# Wisp_v02.net
KiCad netlist of a schematic drawn in EAGLE
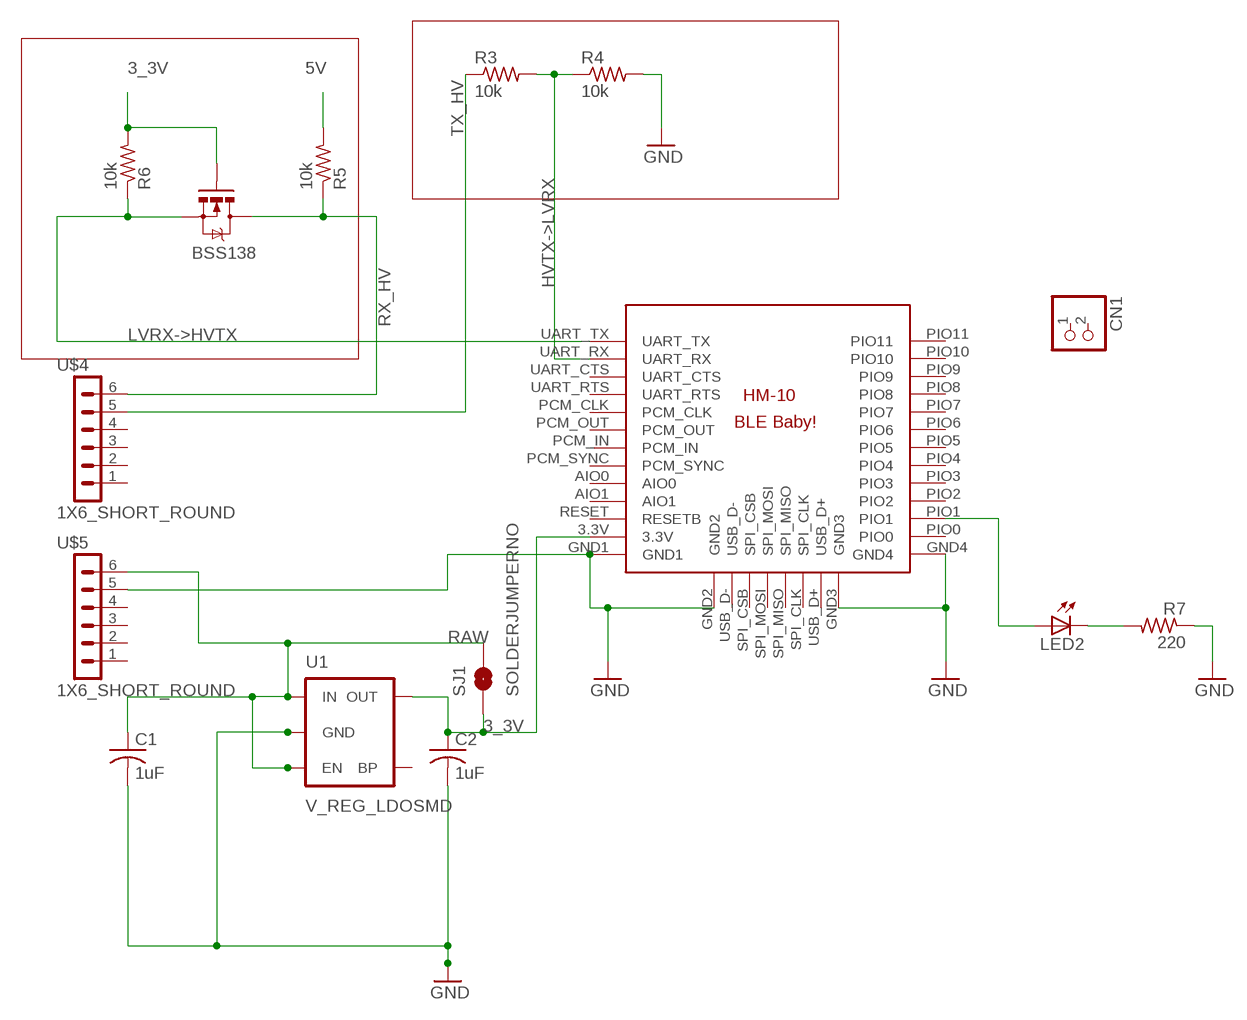
[diagram p0: schematic, sheet 1]

(export (version "E")
  (design (tool "Eeschema 10.0.6"))
  (components
    (comp (ref "BSS138")
      (value "MOSFET-NCHANNELSMD")
      (footprint "eagle-import:SOT23-3")
      (libsource (lib "eagle-import") (part "MOSFET-NCHANNELSMD"))
    )
    (comp (ref "C1")
      (value "1uF")
      (footprint "eagle-import:C0805K")
      (libsource (lib "eagle-import") (part "C-USC0805K"))
    )
    (comp (ref "C2")
      (value "1uF")
      (footprint "eagle-import:C0805K")
      (libsource (lib "eagle-import") (part "C-USC0805K"))
    )
    (comp (ref "CN1")
      (value "JST_2PIN-SMT")
      (footprint "eagle-import:JST-PH-2-SMT")
      (libsource (lib "eagle-import") (part "JST_2PIN-SMT"))
    )
    (comp (ref "LED2")
      (value "LED0603")
      (footprint "eagle-import:LED-0603")
      (libsource (lib "eagle-import") (part "LED0603"))
    )
    (comp (ref "R3")
      (value "10k")
      (footprint "eagle-import:M0805")
      (libsource (lib "eagle-import") (part "R-US_M0805"))
    )
    (comp (ref "R4")
      (value "10k")
      (footprint "eagle-import:M0805")
      (libsource (lib "eagle-import") (part "R-US_M0805"))
    )
    (comp (ref "R5")
      (value "10k")
      (footprint "eagle-import:M0805")
      (libsource (lib "eagle-import") (part "R-US_M0805"))
    )
    (comp (ref "R6")
      (value "10k")
      (footprint "eagle-import:M0805")
      (libsource (lib "eagle-import") (part "R-US_M0805"))
    )
    (comp (ref "R7")
      (value "220")
      (footprint "eagle-import:M0805")
      (libsource (lib "eagle-import") (part "R-US_M0805"))
    )
    (comp (ref "SJ1")
      (value "SOLDERJUMPERNO")
      (footprint "eagle-import:SJ_2S-NO")
      (libsource (lib "eagle-import") (part "SOLDERJUMPERNO"))
    )
    (comp (ref "U$1")
      (value "BLE-HM-10")
      (footprint "eagle-import:BLE-HM-10")
      (libsource (lib "eagle-import") (part "BLE-HM-10"))
    )
    (comp (ref "U$4")
      (value "1X6_SHORT_ROUND")
      (footprint "eagle-import:1X6_SHORT_ROUND")
      (libsource (lib "eagle-import") (part "1X6_SHORT_ROUND"))
    )
    (comp (ref "U$5")
      (value "1X6_SHORT_ROUND")
      (footprint "eagle-import:1X6_SHORT_ROUND")
      (libsource (lib "eagle-import") (part "1X6_SHORT_ROUND"))
    )
    (comp (ref "U1")
      (value "V_REG_LDOSMD")
      (footprint "eagle-import:SOT23-5")
      (libsource (lib "eagle-import") (part "V_REG_LDOSMD"))
    )
  )
  (nets
    (net (code "1") (name "/3_3V") (class "Default")
      (node (ref "BSS138") (pin "1") (pinfunction "G_1") (pintype "passive"))
      (node (ref "C2") (pin "1") (pinfunction "1_1") (pintype "passive"))
      (node (ref "R6") (pin "2") (pinfunction "2_2") (pintype "passive"))
      (node (ref "SJ1") (pin "1") (pinfunction "1_1") (pintype "passive"))
      (node (ref "U$1") (pin "3.3V") (pinfunction "3.3V_3.3V") (pintype "bidirectional"))
      (node (ref "U1") (pin "5") (pinfunction "OUT_5") (pintype "passive"))
    )
    (net (code "2") (name "/5V") (class "Default")
      (node (ref "R5") (pin "2") (pinfunction "2_2") (pintype "passive"))
    )
    (net (code "3") (name "/HVTX->LVRX") (class "Default")
      (node (ref "R3") (pin "2") (pinfunction "2_2") (pintype "passive"))
      (node (ref "R4") (pin "1") (pinfunction "1_1") (pintype "passive"))
      (node (ref "U$1") (pin "UART_RX") (pinfunction "UART_RX_UART_RX") (pintype "bidirectional"))
    )
    (net (code "4") (name "/LVRX->HVTX") (class "Default")
      (node (ref "BSS138") (pin "2") (pinfunction "S_2") (pintype "passive"))
      (node (ref "R6") (pin "1") (pinfunction "1_1") (pintype "passive"))
      (node (ref "U$1") (pin "UART_TX") (pinfunction "UART_TX_UART_TX") (pintype "bidirectional"))
    )
    (net (code "5") (name "/RAW") (class "Default")
      (node (ref "C1") (pin "1") (pinfunction "1_1") (pintype "passive"))
      (node (ref "SJ1") (pin "2") (pinfunction "2_2") (pintype "passive"))
      (node (ref "U$5") (pin "6") (pinfunction "6_6") (pintype "passive"))
      (node (ref "U1") (pin "1") (pinfunction "IN_1") (pintype "input"))
      (node (ref "U1") (pin "3") (pinfunction "EN_3") (pintype "input"))
    )
    (net (code "6") (name "/RX_HV") (class "Default")
      (node (ref "BSS138") (pin "3") (pinfunction "D_3") (pintype "passive"))
      (node (ref "R5") (pin "1") (pinfunction "1_1") (pintype "passive"))
      (node (ref "U$4") (pin "6") (pinfunction "6_6") (pintype "passive"))
    )
    (net (code "7") (name "/TX_HV") (class "Default")
      (node (ref "R3") (pin "1") (pinfunction "1_1") (pintype "passive"))
      (node (ref "U$4") (pin "5") (pinfunction "5_5") (pintype "passive"))
    )
    (net (code "8") (name "GND") (class "Default")
      (node (ref "C1") (pin "2") (pinfunction "2_2") (pintype "passive"))
      (node (ref "C2") (pin "2") (pinfunction "2_2") (pintype "passive"))
      (node (ref "R4") (pin "2") (pinfunction "2_2") (pintype "passive"))
      (node (ref "R7") (pin "1") (pinfunction "1_1") (pintype "passive"))
      (node (ref "U$1") (pin "GND1") (pinfunction "GND1_GND1") (pintype "bidirectional"))
      (node (ref "U$1") (pin "GND2") (pinfunction "GND2_GND2") (pintype "bidirectional"))
      (node (ref "U$1") (pin "GND3") (pinfunction "GND3_GND3") (pintype "bidirectional"))
      (node (ref "U$1") (pin "GND4") (pinfunction "GND4_GND4") (pintype "bidirectional"))
      (node (ref "U$5") (pin "5") (pinfunction "5_5") (pintype "passive"))
      (node (ref "U1") (pin "2") (pinfunction "GND_2") (pintype "input"))
    )
    (net (code "9") (name "Net-(LED2-PadA)") (class "Default")
      (node (ref "LED2") (pin "A") (pinfunction "A_A") (pintype "passive"))
      (node (ref "U$1") (pin "PIO1") (pinfunction "PIO1_PIO1") (pintype "bidirectional"))
    )
    (net (code "10") (name "Net-(LED2-PadC)") (class "Default")
      (node (ref "LED2") (pin "C") (pinfunction "C_C") (pintype "passive"))
      (node (ref "R7") (pin "2") (pinfunction "2_2") (pintype "passive"))
    )
    (net (code "11") (name "unconnected-(CN1-1-Pad2)") (class "Default")
      (node (ref "CN1") (pin "2") (pinfunction "1_2") (pintype "passive"))
    )
    (net (code "12") (name "unconnected-(CN1-2-Pad1)") (class "Default")
      (node (ref "CN1") (pin "1") (pinfunction "2_1") (pintype "passive"))
    )
    (net (code "13") (name "unconnected-(U$1-PadAIO0)") (class "Default")
      (node (ref "U$1") (pin "AIO0") (pinfunction "AIO0_AIO0") (pintype "bidirectional"))
    )
    (net (code "14") (name "unconnected-(U$1-PadAIO1)") (class "Default")
      (node (ref "U$1") (pin "AIO1") (pinfunction "AIO1_AIO1") (pintype "bidirectional"))
    )
    (net (code "15") (name "unconnected-(U$1-PadPCM_CLK)") (class "Default")
      (node (ref "U$1") (pin "PCM_CLK") (pinfunction "PCM_CLK_PCM_CLK") (pintype "bidirectional"))
    )
    (net (code "16") (name "unconnected-(U$1-PadPCM_IN)") (class "Default")
      (node (ref "U$1") (pin "PCM_IN") (pinfunction "PCM_IN_PCM_IN") (pintype "bidirectional"))
    )
    (net (code "17") (name "unconnected-(U$1-PadPCM_OUT)") (class "Default")
      (node (ref "U$1") (pin "PCM_OUT") (pinfunction "PCM_OUT_PCM_OUT") (pintype "bidirectional"))
    )
    (net (code "18") (name "unconnected-(U$1-PadPCM_SYNC)") (class "Default")
      (node (ref "U$1") (pin "PCM_SYNC") (pinfunction "PCM_SYNC_PCM_SYNC") (pintype "bidirectional"))
    )
    (net (code "19") (name "unconnected-(U$1-PadPIO0)") (class "Default")
      (node (ref "U$1") (pin "PIO0") (pinfunction "PIO0_PIO0") (pintype "bidirectional"))
    )
    (net (code "20") (name "unconnected-(U$1-PadPIO2)") (class "Default")
      (node (ref "U$1") (pin "PIO2") (pinfunction "PIO2_PIO2") (pintype "bidirectional"))
    )
    (net (code "21") (name "unconnected-(U$1-PadPIO3)") (class "Default")
      (node (ref "U$1") (pin "PIO3") (pinfunction "PIO3_PIO3") (pintype "bidirectional"))
    )
    (net (code "22") (name "unconnected-(U$1-PadPIO4)") (class "Default")
      (node (ref "U$1") (pin "PIO4") (pinfunction "PIO4_PIO4") (pintype "bidirectional"))
    )
    (net (code "23") (name "unconnected-(U$1-PadPIO5)") (class "Default")
      (node (ref "U$1") (pin "PIO5") (pinfunction "PIO5_PIO5") (pintype "bidirectional"))
    )
    (net (code "24") (name "unconnected-(U$1-PadPIO6)") (class "Default")
      (node (ref "U$1") (pin "PIO6") (pinfunction "PIO6_PIO6") (pintype "bidirectional"))
    )
    (net (code "25") (name "unconnected-(U$1-PadPIO7)") (class "Default")
      (node (ref "U$1") (pin "PIO7") (pinfunction "PIO7_PIO7") (pintype "bidirectional"))
    )
    (net (code "26") (name "unconnected-(U$1-PadPIO8)") (class "Default")
      (node (ref "U$1") (pin "PIO8") (pinfunction "PIO8_PIO8") (pintype "bidirectional"))
    )
    (net (code "27") (name "unconnected-(U$1-PadPIO9)") (class "Default")
      (node (ref "U$1") (pin "PIO9") (pinfunction "PIO9_PIO9") (pintype "bidirectional"))
    )
    (net (code "28") (name "unconnected-(U$1-PadPIO10)") (class "Default")
      (node (ref "U$1") (pin "PIO10") (pinfunction "PIO10_PIO10") (pintype "bidirectional"))
    )
    (net (code "29") (name "unconnected-(U$1-PadPIO11)") (class "Default")
      (node (ref "U$1") (pin "PIO11") (pinfunction "PIO11_PIO11") (pintype "bidirectional"))
    )
    (net (code "30") (name "unconnected-(U$1-PadSPI_CLK)") (class "Default")
      (node (ref "U$1") (pin "SPI_CLK") (pinfunction "SPI_CLK_SPI_CLK") (pintype "bidirectional"))
    )
    (net (code "31") (name "unconnected-(U$1-PadSPI_CSB)") (class "Default")
      (node (ref "U$1") (pin "SPI_CSB") (pinfunction "SPI_CSB_SPI_CSB") (pintype "bidirectional"))
    )
    (net (code "32") (name "unconnected-(U$1-PadSPI_MISO)") (class "Default")
      (node (ref "U$1") (pin "SPI_MISO") (pinfunction "SPI_MISO_SPI_MISO") (pintype "bidirectional"))
    )
    (net (code "33") (name "unconnected-(U$1-PadSPI_MOSI)") (class "Default")
      (node (ref "U$1") (pin "SPI_MOSI") (pinfunction "SPI_MOSI_SPI_MOSI") (pintype "bidirectional"))
    )
    (net (code "34") (name "unconnected-(U$1-PadUART_CTS)") (class "Default")
      (node (ref "U$1") (pin "UART_CTS") (pinfunction "UART_CTS_UART_CTS") (pintype "bidirectional"))
    )
    (net (code "35") (name "unconnected-(U$1-PadUART_RTS)") (class "Default")
      (node (ref "U$1") (pin "UART_RTS") (pinfunction "UART_RTS_UART_RTS") (pintype "bidirectional"))
    )
    (net (code "36") (name "unconnected-(U$1-PadUSB_D+)") (class "Default")
      (node (ref "U$1") (pin "USB_D+") (pinfunction "USB_D+_USB_D+") (pintype "bidirectional"))
    )
    (net (code "37") (name "unconnected-(U$1-PadUSB_D-)") (class "Default")
      (node (ref "U$1") (pin "USB_D-") (pinfunction "USB_D-_USB_D-") (pintype "bidirectional"))
    )
    (net (code "38") (name "unconnected-(U$1-RESETB-PadRESET)") (class "Default")
      (node (ref "U$1") (pin "RESET") (pinfunction "RESETB_RESET") (pintype "bidirectional"))
    )
    (net (code "39") (name "unconnected-(U$4-Pad1)") (class "Default")
      (node (ref "U$4") (pin "1") (pinfunction "1_1") (pintype "passive"))
    )
    (net (code "40") (name "unconnected-(U$4-Pad2)") (class "Default")
      (node (ref "U$4") (pin "2") (pinfunction "2_2") (pintype "passive"))
    )
    (net (code "41") (name "unconnected-(U$4-Pad3)") (class "Default")
      (node (ref "U$4") (pin "3") (pinfunction "3_3") (pintype "passive"))
    )
    (net (code "42") (name "unconnected-(U$4-Pad4)") (class "Default")
      (node (ref "U$4") (pin "4") (pinfunction "4_4") (pintype "passive"))
    )
    (net (code "43") (name "unconnected-(U$5-Pad1)") (class "Default")
      (node (ref "U$5") (pin "1") (pinfunction "1_1") (pintype "passive"))
    )
    (net (code "44") (name "unconnected-(U$5-Pad2)") (class "Default")
      (node (ref "U$5") (pin "2") (pinfunction "2_2") (pintype "passive"))
    )
    (net (code "45") (name "unconnected-(U$5-Pad3)") (class "Default")
      (node (ref "U$5") (pin "3") (pinfunction "3_3") (pintype "passive"))
    )
    (net (code "46") (name "unconnected-(U$5-Pad4)") (class "Default")
      (node (ref "U$5") (pin "4") (pinfunction "4_4") (pintype "passive"))
    )
    (net (code "47") (name "unconnected-(U1-BP-Pad4)") (class "Default")
      (node (ref "U1") (pin "4") (pinfunction "BP_4") (pintype "input"))
    )
  )
)
